# MemoryChip.net
KiCad netlist of a schematic drawn in Altium Designer
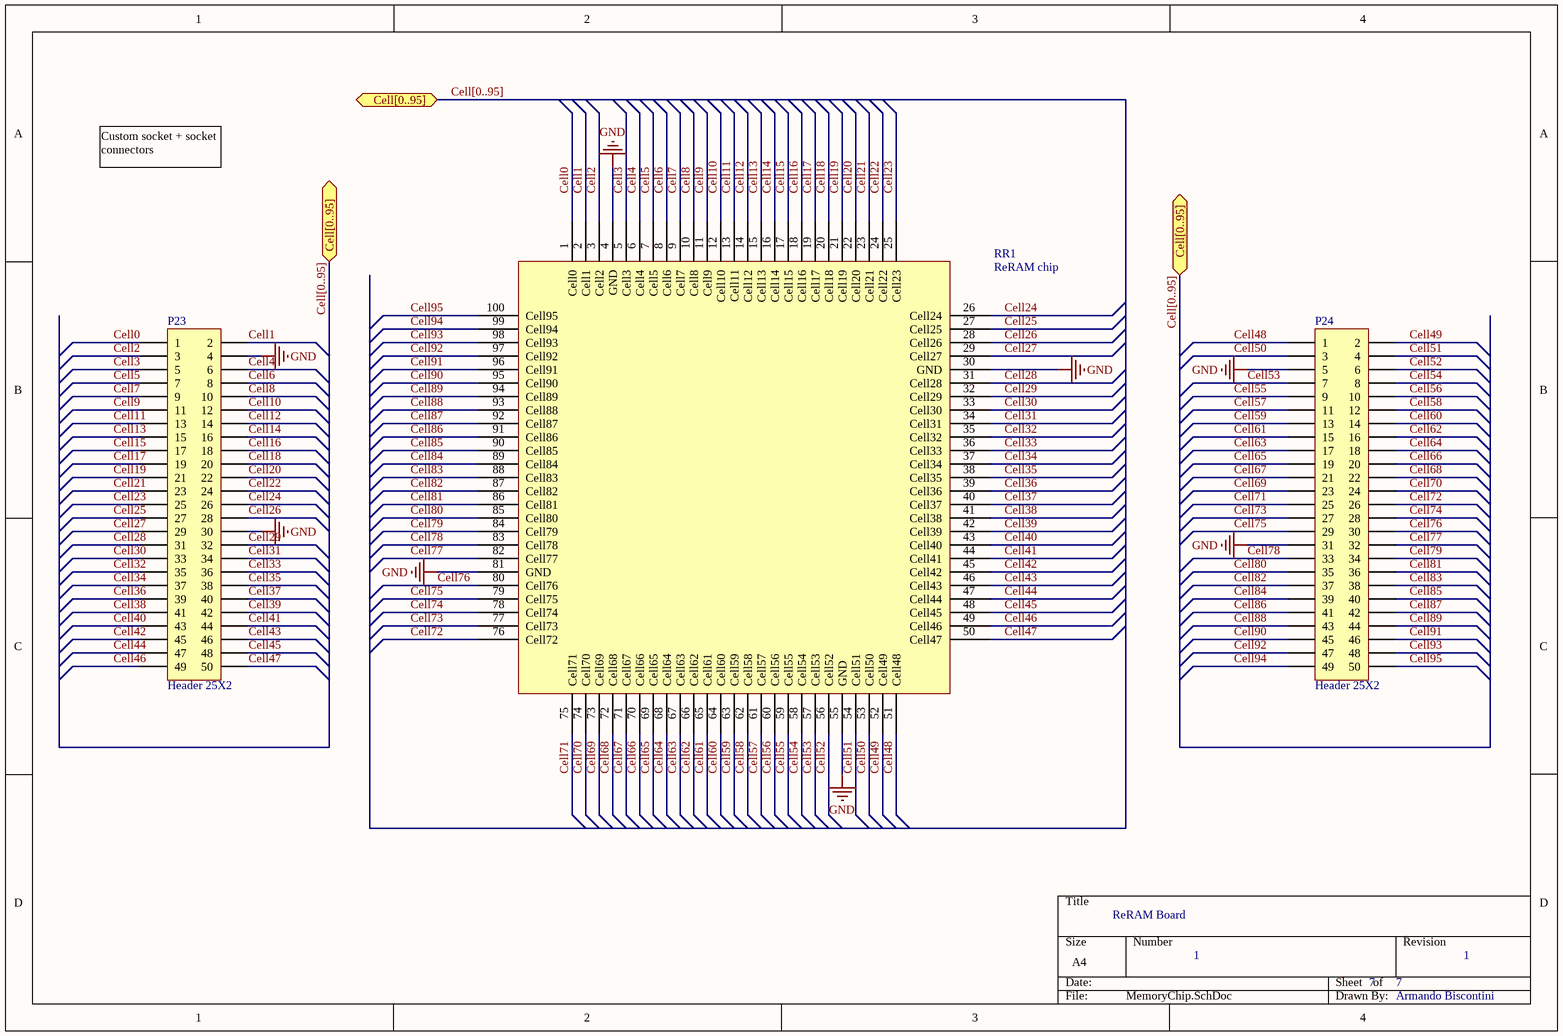
[diagram p0: MemoryChip.SchDoc]

(export (version "E")
  (design (tool "Eeschema 10.0.6"))
  (components
    (comp (ref "P23")
      (value "Header 25X2")
      (footprint "HDR2X25")
      (description "Header, 25-Pin, Dual row")
      (fields (field (name "PUBLISHER") "Altium Limited"))
      (libsource (lib "Miscellaneous Connectors") (part "Header 25X2"))
    )
    (comp (ref "P24")
      (value "Header 25X2")
      (footprint "HDR2X25")
      (description "Header, 25-Pin, Dual row")
      (fields (field (name "PUBLISHER") "Altium Limited"))
      (libsource (lib "Miscellaneous Connectors") (part "Header 25X2"))
    )
    (comp (ref "RR1")
      (value "ReRAM chip")
      (footprint "LSI-PLLGA100")
      (description "ReRAM chip on LSI-PLLGA100 custom socket")
      (libsource (lib "ReRAM_Board_library") (part "ReRAM_LSI-PLLGA100"))
    )
  )
  (nets
    (net (code "1") (name "/Cell0") (class "Default")
      (node (ref "P23") (pin "1") (pinfunction "1_1") (pintype "passive"))
      (node (ref "RR1") (pin "1") (pinfunction "Cell0_1") (pintype "passive"))
    )
    (net (code "2") (name "/Cell1") (class "Default")
      (node (ref "P23") (pin "2") (pinfunction "2_2") (pintype "passive"))
      (node (ref "RR1") (pin "2") (pinfunction "Cell1_2") (pintype "passive"))
    )
    (net (code "3") (name "/Cell2") (class "Default")
      (node (ref "P23") (pin "3") (pinfunction "3_3") (pintype "passive"))
      (node (ref "RR1") (pin "3") (pinfunction "Cell2_3") (pintype "passive"))
    )
    (net (code "4") (name "/Cell3") (class "Default")
      (node (ref "P23") (pin "5") (pinfunction "5_5") (pintype "passive"))
      (node (ref "RR1") (pin "5") (pinfunction "Cell3_5") (pintype "passive"))
    )
    (net (code "5") (name "/Cell4") (class "Default")
      (node (ref "P23") (pin "6") (pinfunction "6_6") (pintype "passive"))
      (node (ref "RR1") (pin "6") (pinfunction "Cell4_6") (pintype "passive"))
    )
    (net (code "6") (name "/Cell5") (class "Default")
      (node (ref "P23") (pin "7") (pinfunction "7_7") (pintype "passive"))
      (node (ref "RR1") (pin "7") (pinfunction "Cell5_7") (pintype "passive"))
    )
    (net (code "7") (name "/Cell6") (class "Default")
      (node (ref "P23") (pin "8") (pinfunction "8_8") (pintype "passive"))
      (node (ref "RR1") (pin "8") (pinfunction "Cell6_8") (pintype "passive"))
    )
    (net (code "8") (name "/Cell7") (class "Default")
      (node (ref "P23") (pin "9") (pinfunction "9_9") (pintype "passive"))
      (node (ref "RR1") (pin "9") (pinfunction "Cell7_9") (pintype "passive"))
    )
    (net (code "9") (name "/Cell8") (class "Default")
      (node (ref "P23") (pin "10") (pinfunction "10_10") (pintype "passive"))
      (node (ref "RR1") (pin "10") (pinfunction "Cell8_10") (pintype "passive"))
    )
    (net (code "10") (name "/Cell9") (class "Default")
      (node (ref "P23") (pin "11") (pinfunction "11_11") (pintype "passive"))
      (node (ref "RR1") (pin "11") (pinfunction "Cell9_11") (pintype "passive"))
    )
    (net (code "11") (name "/Cell10") (class "Default")
      (node (ref "P23") (pin "12") (pinfunction "12_12") (pintype "passive"))
      (node (ref "RR1") (pin "12") (pinfunction "Cell10_12") (pintype "passive"))
    )
    (net (code "12") (name "/Cell11") (class "Default")
      (node (ref "P23") (pin "13") (pinfunction "13_13") (pintype "passive"))
      (node (ref "RR1") (pin "13") (pinfunction "Cell11_13") (pintype "passive"))
    )
    (net (code "13") (name "/Cell12") (class "Default")
      (node (ref "P23") (pin "14") (pinfunction "14_14") (pintype "passive"))
      (node (ref "RR1") (pin "14") (pinfunction "Cell12_14") (pintype "passive"))
    )
    (net (code "14") (name "/Cell13") (class "Default")
      (node (ref "P23") (pin "15") (pinfunction "15_15") (pintype "passive"))
      (node (ref "RR1") (pin "15") (pinfunction "Cell13_15") (pintype "passive"))
    )
    (net (code "15") (name "/Cell14") (class "Default")
      (node (ref "P23") (pin "16") (pinfunction "16_16") (pintype "passive"))
      (node (ref "RR1") (pin "16") (pinfunction "Cell14_16") (pintype "passive"))
    )
    (net (code "16") (name "/Cell15") (class "Default")
      (node (ref "P23") (pin "17") (pinfunction "17_17") (pintype "passive"))
      (node (ref "RR1") (pin "17") (pinfunction "Cell15_17") (pintype "passive"))
    )
    (net (code "17") (name "/Cell16") (class "Default")
      (node (ref "P23") (pin "18") (pinfunction "18_18") (pintype "passive"))
      (node (ref "RR1") (pin "18") (pinfunction "Cell16_18") (pintype "passive"))
    )
    (net (code "18") (name "/Cell17") (class "Default")
      (node (ref "P23") (pin "19") (pinfunction "19_19") (pintype "passive"))
      (node (ref "RR1") (pin "19") (pinfunction "Cell17_19") (pintype "passive"))
    )
    (net (code "19") (name "/Cell18") (class "Default")
      (node (ref "P23") (pin "20") (pinfunction "20_20") (pintype "passive"))
      (node (ref "RR1") (pin "20") (pinfunction "Cell18_20") (pintype "passive"))
    )
    (net (code "20") (name "/Cell19") (class "Default")
      (node (ref "P23") (pin "21") (pinfunction "21_21") (pintype "passive"))
      (node (ref "RR1") (pin "21") (pinfunction "Cell19_21") (pintype "passive"))
    )
    (net (code "21") (name "/Cell20") (class "Default")
      (node (ref "P23") (pin "22") (pinfunction "22_22") (pintype "passive"))
      (node (ref "RR1") (pin "22") (pinfunction "Cell20_22") (pintype "passive"))
    )
    (net (code "22") (name "/Cell21") (class "Default")
      (node (ref "P23") (pin "23") (pinfunction "23_23") (pintype "passive"))
      (node (ref "RR1") (pin "23") (pinfunction "Cell21_23") (pintype "passive"))
    )
    (net (code "23") (name "/Cell22") (class "Default")
      (node (ref "P23") (pin "24") (pinfunction "24_24") (pintype "passive"))
      (node (ref "RR1") (pin "24") (pinfunction "Cell22_24") (pintype "passive"))
    )
    (net (code "24") (name "/Cell23") (class "Default")
      (node (ref "P23") (pin "25") (pinfunction "25_25") (pintype "passive"))
      (node (ref "RR1") (pin "25") (pinfunction "Cell23_25") (pintype "passive"))
    )
    (net (code "25") (name "/Cell24") (class "Default")
      (node (ref "P23") (pin "26") (pinfunction "26_26") (pintype "passive"))
      (node (ref "RR1") (pin "26") (pinfunction "Cell24_26") (pintype "passive"))
    )
    (net (code "26") (name "/Cell25") (class "Default")
      (node (ref "P23") (pin "27") (pinfunction "27_27") (pintype "passive"))
      (node (ref "RR1") (pin "27") (pinfunction "Cell25_27") (pintype "passive"))
    )
    (net (code "27") (name "/Cell26") (class "Default")
      (node (ref "P23") (pin "28") (pinfunction "28_28") (pintype "passive"))
      (node (ref "RR1") (pin "28") (pinfunction "Cell26_28") (pintype "passive"))
    )
    (net (code "28") (name "/Cell27") (class "Default")
      (node (ref "P23") (pin "29") (pinfunction "29_29") (pintype "passive"))
      (node (ref "RR1") (pin "29") (pinfunction "Cell27_29") (pintype "passive"))
    )
    (net (code "29") (name "/Cell28") (class "Default")
      (node (ref "P23") (pin "31") (pinfunction "31_31") (pintype "passive"))
      (node (ref "RR1") (pin "31") (pinfunction "Cell28_31") (pintype "passive"))
    )
    (net (code "30") (name "/Cell29") (class "Default")
      (node (ref "P23") (pin "32") (pinfunction "32_32") (pintype "passive"))
      (node (ref "RR1") (pin "32") (pinfunction "Cell29_32") (pintype "passive"))
    )
    (net (code "31") (name "/Cell30") (class "Default")
      (node (ref "P23") (pin "33") (pinfunction "33_33") (pintype "passive"))
      (node (ref "RR1") (pin "33") (pinfunction "Cell30_33") (pintype "passive"))
    )
    (net (code "32") (name "/Cell31") (class "Default")
      (node (ref "P23") (pin "34") (pinfunction "34_34") (pintype "passive"))
      (node (ref "RR1") (pin "34") (pinfunction "Cell31_34") (pintype "passive"))
    )
    (net (code "33") (name "/Cell32") (class "Default")
      (node (ref "P23") (pin "35") (pinfunction "35_35") (pintype "passive"))
      (node (ref "RR1") (pin "35") (pinfunction "Cell32_35") (pintype "passive"))
    )
    (net (code "34") (name "/Cell33") (class "Default")
      (node (ref "P23") (pin "36") (pinfunction "36_36") (pintype "passive"))
      (node (ref "RR1") (pin "36") (pinfunction "Cell33_36") (pintype "passive"))
    )
    (net (code "35") (name "/Cell34") (class "Default")
      (node (ref "P23") (pin "37") (pinfunction "37_37") (pintype "passive"))
      (node (ref "RR1") (pin "37") (pinfunction "Cell34_37") (pintype "passive"))
    )
    (net (code "36") (name "/Cell35") (class "Default")
      (node (ref "P23") (pin "38") (pinfunction "38_38") (pintype "passive"))
      (node (ref "RR1") (pin "38") (pinfunction "Cell35_38") (pintype "passive"))
    )
    (net (code "37") (name "/Cell36") (class "Default")
      (node (ref "P23") (pin "39") (pinfunction "39_39") (pintype "passive"))
      (node (ref "RR1") (pin "39") (pinfunction "Cell36_39") (pintype "passive"))
    )
    (net (code "38") (name "/Cell37") (class "Default")
      (node (ref "P23") (pin "40") (pinfunction "40_40") (pintype "passive"))
      (node (ref "RR1") (pin "40") (pinfunction "Cell37_40") (pintype "passive"))
    )
    (net (code "39") (name "/Cell38") (class "Default")
      (node (ref "P23") (pin "41") (pinfunction "41_41") (pintype "passive"))
      (node (ref "RR1") (pin "41") (pinfunction "Cell38_41") (pintype "passive"))
    )
    (net (code "40") (name "/Cell39") (class "Default")
      (node (ref "P23") (pin "42") (pinfunction "42_42") (pintype "passive"))
      (node (ref "RR1") (pin "42") (pinfunction "Cell39_42") (pintype "passive"))
    )
    (net (code "41") (name "/Cell40") (class "Default")
      (node (ref "P23") (pin "43") (pinfunction "43_43") (pintype "passive"))
      (node (ref "RR1") (pin "43") (pinfunction "Cell40_43") (pintype "passive"))
    )
    (net (code "42") (name "/Cell41") (class "Default")
      (node (ref "P23") (pin "44") (pinfunction "44_44") (pintype "passive"))
      (node (ref "RR1") (pin "44") (pinfunction "Cell41_44") (pintype "passive"))
    )
    (net (code "43") (name "/Cell42") (class "Default")
      (node (ref "P23") (pin "45") (pinfunction "45_45") (pintype "passive"))
      (node (ref "RR1") (pin "45") (pinfunction "Cell42_45") (pintype "passive"))
    )
    (net (code "44") (name "/Cell43") (class "Default")
      (node (ref "P23") (pin "46") (pinfunction "46_46") (pintype "passive"))
      (node (ref "RR1") (pin "46") (pinfunction "Cell43_46") (pintype "passive"))
    )
    (net (code "45") (name "/Cell44") (class "Default")
      (node (ref "P23") (pin "47") (pinfunction "47_47") (pintype "passive"))
      (node (ref "RR1") (pin "47") (pinfunction "Cell44_47") (pintype "passive"))
    )
    (net (code "46") (name "/Cell45") (class "Default")
      (node (ref "P23") (pin "48") (pinfunction "48_48") (pintype "passive"))
      (node (ref "RR1") (pin "48") (pinfunction "Cell45_48") (pintype "passive"))
    )
    (net (code "47") (name "/Cell46") (class "Default")
      (node (ref "P23") (pin "49") (pinfunction "49_49") (pintype "passive"))
      (node (ref "RR1") (pin "49") (pinfunction "Cell46_49") (pintype "passive"))
    )
    (net (code "48") (name "/Cell47") (class "Default")
      (node (ref "P23") (pin "50") (pinfunction "50_50") (pintype "passive"))
      (node (ref "RR1") (pin "50") (pinfunction "Cell47_50") (pintype "passive"))
    )
    (net (code "49") (name "/Cell48") (class "Default")
      (node (ref "P24") (pin "1") (pinfunction "1_1") (pintype "passive"))
      (node (ref "RR1") (pin "51") (pinfunction "Cell48_51") (pintype "passive"))
    )
    (net (code "50") (name "/Cell49") (class "Default")
      (node (ref "P24") (pin "2") (pinfunction "2_2") (pintype "passive"))
      (node (ref "RR1") (pin "52") (pinfunction "Cell49_52") (pintype "passive"))
    )
    (net (code "51") (name "/Cell50") (class "Default")
      (node (ref "P24") (pin "3") (pinfunction "3_3") (pintype "passive"))
      (node (ref "RR1") (pin "53") (pinfunction "Cell50_53") (pintype "passive"))
    )
    (net (code "52") (name "/Cell51") (class "Default")
      (node (ref "P24") (pin "4") (pinfunction "4_4") (pintype "passive"))
      (node (ref "RR1") (pin "54") (pinfunction "Cell51_54") (pintype "passive"))
    )
    (net (code "53") (name "/Cell52") (class "Default")
      (node (ref "P24") (pin "6") (pinfunction "6_6") (pintype "passive"))
      (node (ref "RR1") (pin "56") (pinfunction "Cell52_56") (pintype "passive"))
    )
    (net (code "54") (name "/Cell53") (class "Default")
      (node (ref "P24") (pin "7") (pinfunction "7_7") (pintype "passive"))
      (node (ref "RR1") (pin "57") (pinfunction "Cell53_57") (pintype "passive"))
    )
    (net (code "55") (name "/Cell54") (class "Default")
      (node (ref "P24") (pin "8") (pinfunction "8_8") (pintype "passive"))
      (node (ref "RR1") (pin "58") (pinfunction "Cell54_58") (pintype "passive"))
    )
    (net (code "56") (name "/Cell55") (class "Default")
      (node (ref "P24") (pin "9") (pinfunction "9_9") (pintype "passive"))
      (node (ref "RR1") (pin "59") (pinfunction "Cell55_59") (pintype "passive"))
    )
    (net (code "57") (name "/Cell56") (class "Default")
      (node (ref "P24") (pin "10") (pinfunction "10_10") (pintype "passive"))
      (node (ref "RR1") (pin "60") (pinfunction "Cell56_60") (pintype "passive"))
    )
    (net (code "58") (name "/Cell57") (class "Default")
      (node (ref "P24") (pin "11") (pinfunction "11_11") (pintype "passive"))
      (node (ref "RR1") (pin "61") (pinfunction "Cell57_61") (pintype "passive"))
    )
    (net (code "59") (name "/Cell58") (class "Default")
      (node (ref "P24") (pin "12") (pinfunction "12_12") (pintype "passive"))
      (node (ref "RR1") (pin "62") (pinfunction "Cell58_62") (pintype "passive"))
    )
    (net (code "60") (name "/Cell59") (class "Default")
      (node (ref "P24") (pin "13") (pinfunction "13_13") (pintype "passive"))
      (node (ref "RR1") (pin "63") (pinfunction "Cell59_63") (pintype "passive"))
    )
    (net (code "61") (name "/Cell60") (class "Default")
      (node (ref "P24") (pin "14") (pinfunction "14_14") (pintype "passive"))
      (node (ref "RR1") (pin "64") (pinfunction "Cell60_64") (pintype "passive"))
    )
    (net (code "62") (name "/Cell61") (class "Default")
      (node (ref "P24") (pin "15") (pinfunction "15_15") (pintype "passive"))
      (node (ref "RR1") (pin "65") (pinfunction "Cell61_65") (pintype "passive"))
    )
    (net (code "63") (name "/Cell62") (class "Default")
      (node (ref "P24") (pin "16") (pinfunction "16_16") (pintype "passive"))
      (node (ref "RR1") (pin "66") (pinfunction "Cell62_66") (pintype "passive"))
    )
    (net (code "64") (name "/Cell63") (class "Default")
      (node (ref "P24") (pin "17") (pinfunction "17_17") (pintype "passive"))
      (node (ref "RR1") (pin "67") (pinfunction "Cell63_67") (pintype "passive"))
    )
    (net (code "65") (name "/Cell64") (class "Default")
      (node (ref "P24") (pin "18") (pinfunction "18_18") (pintype "passive"))
      (node (ref "RR1") (pin "68") (pinfunction "Cell64_68") (pintype "passive"))
    )
    (net (code "66") (name "/Cell65") (class "Default")
      (node (ref "P24") (pin "19") (pinfunction "19_19") (pintype "passive"))
      (node (ref "RR1") (pin "69") (pinfunction "Cell65_69") (pintype "passive"))
    )
    (net (code "67") (name "/Cell66") (class "Default")
      (node (ref "P24") (pin "20") (pinfunction "20_20") (pintype "passive"))
      (node (ref "RR1") (pin "70") (pinfunction "Cell66_70") (pintype "passive"))
    )
    (net (code "68") (name "/Cell67") (class "Default")
      (node (ref "P24") (pin "21") (pinfunction "21_21") (pintype "passive"))
      (node (ref "RR1") (pin "71") (pinfunction "Cell67_71") (pintype "passive"))
    )
    (net (code "69") (name "/Cell68") (class "Default")
      (node (ref "P24") (pin "22") (pinfunction "22_22") (pintype "passive"))
      (node (ref "RR1") (pin "72") (pinfunction "Cell68_72") (pintype "passive"))
    )
    (net (code "70") (name "/Cell69") (class "Default")
      (node (ref "P24") (pin "23") (pinfunction "23_23") (pintype "passive"))
      (node (ref "RR1") (pin "73") (pinfunction "Cell69_73") (pintype "passive"))
    )
    (net (code "71") (name "/Cell70") (class "Default")
      (node (ref "P24") (pin "24") (pinfunction "24_24") (pintype "passive"))
      (node (ref "RR1") (pin "74") (pinfunction "Cell70_74") (pintype "passive"))
    )
    (net (code "72") (name "/Cell71") (class "Default")
      (node (ref "P24") (pin "25") (pinfunction "25_25") (pintype "passive"))
      (node (ref "RR1") (pin "75") (pinfunction "Cell71_75") (pintype "passive"))
    )
    (net (code "73") (name "/Cell72") (class "Default")
      (node (ref "P24") (pin "26") (pinfunction "26_26") (pintype "passive"))
      (node (ref "RR1") (pin "76") (pinfunction "Cell72_76") (pintype "passive"))
    )
    (net (code "74") (name "/Cell73") (class "Default")
      (node (ref "P24") (pin "27") (pinfunction "27_27") (pintype "passive"))
      (node (ref "RR1") (pin "77") (pinfunction "Cell73_77") (pintype "passive"))
    )
    (net (code "75") (name "/Cell74") (class "Default")
      (node (ref "P24") (pin "28") (pinfunction "28_28") (pintype "passive"))
      (node (ref "RR1") (pin "78") (pinfunction "Cell74_78") (pintype "passive"))
    )
    (net (code "76") (name "/Cell75") (class "Default")
      (node (ref "P24") (pin "29") (pinfunction "29_29") (pintype "passive"))
      (node (ref "RR1") (pin "79") (pinfunction "Cell75_79") (pintype "passive"))
    )
    (net (code "77") (name "/Cell76") (class "Default")
      (node (ref "P24") (pin "30") (pinfunction "30_30") (pintype "passive"))
      (node (ref "RR1") (pin "80") (pinfunction "Cell76_80") (pintype "passive"))
    )
    (net (code "78") (name "/Cell77") (class "Default")
      (node (ref "P24") (pin "32") (pinfunction "32_32") (pintype "passive"))
      (node (ref "RR1") (pin "82") (pinfunction "Cell77_82") (pintype "passive"))
    )
    (net (code "79") (name "/Cell78") (class "Default")
      (node (ref "P24") (pin "33") (pinfunction "33_33") (pintype "passive"))
      (node (ref "RR1") (pin "83") (pinfunction "Cell78_83") (pintype "passive"))
    )
    (net (code "80") (name "/Cell79") (class "Default")
      (node (ref "P24") (pin "34") (pinfunction "34_34") (pintype "passive"))
      (node (ref "RR1") (pin "84") (pinfunction "Cell79_84") (pintype "passive"))
    )
    (net (code "81") (name "/Cell80") (class "Default")
      (node (ref "P24") (pin "35") (pinfunction "35_35") (pintype "passive"))
      (node (ref "RR1") (pin "85") (pinfunction "Cell80_85") (pintype "passive"))
    )
    (net (code "82") (name "/Cell81") (class "Default")
      (node (ref "P24") (pin "36") (pinfunction "36_36") (pintype "passive"))
      (node (ref "RR1") (pin "86") (pinfunction "Cell81_86") (pintype "passive"))
    )
    (net (code "83") (name "/Cell82") (class "Default")
      (node (ref "P24") (pin "37") (pinfunction "37_37") (pintype "passive"))
      (node (ref "RR1") (pin "87") (pinfunction "Cell82_87") (pintype "passive"))
    )
    (net (code "84") (name "/Cell83") (class "Default")
      (node (ref "P24") (pin "38") (pinfunction "38_38") (pintype "passive"))
      (node (ref "RR1") (pin "88") (pinfunction "Cell83_88") (pintype "passive"))
    )
    (net (code "85") (name "/Cell84") (class "Default")
      (node (ref "P24") (pin "39") (pinfunction "39_39") (pintype "passive"))
      (node (ref "RR1") (pin "89") (pinfunction "Cell84_89") (pintype "passive"))
    )
    (net (code "86") (name "/Cell85") (class "Default")
      (node (ref "P24") (pin "40") (pinfunction "40_40") (pintype "passive"))
      (node (ref "RR1") (pin "90") (pinfunction "Cell85_90") (pintype "passive"))
    )
    (net (code "87") (name "/Cell86") (class "Default")
      (node (ref "P24") (pin "41") (pinfunction "41_41") (pintype "passive"))
      (node (ref "RR1") (pin "91") (pinfunction "Cell86_91") (pintype "passive"))
    )
    (net (code "88") (name "/Cell87") (class "Default")
      (node (ref "P24") (pin "42") (pinfunction "42_42") (pintype "passive"))
      (node (ref "RR1") (pin "92") (pinfunction "Cell87_92") (pintype "passive"))
    )
    (net (code "89") (name "/Cell88") (class "Default")
      (node (ref "P24") (pin "43") (pinfunction "43_43") (pintype "passive"))
      (node (ref "RR1") (pin "93") (pinfunction "Cell88_93") (pintype "passive"))
    )
    (net (code "90") (name "/Cell89") (class "Default")
      (node (ref "P24") (pin "44") (pinfunction "44_44") (pintype "passive"))
      (node (ref "RR1") (pin "94") (pinfunction "Cell89_94") (pintype "passive"))
    )
    (net (code "91") (name "/Cell90") (class "Default")
      (node (ref "P24") (pin "45") (pinfunction "45_45") (pintype "passive"))
      (node (ref "RR1") (pin "95") (pinfunction "Cell90_95") (pintype "passive"))
    )
    (net (code "92") (name "/Cell91") (class "Default")
      (node (ref "P24") (pin "46") (pinfunction "46_46") (pintype "passive"))
      (node (ref "RR1") (pin "96") (pinfunction "Cell91_96") (pintype "passive"))
    )
    (net (code "93") (name "/Cell92") (class "Default")
      (node (ref "P24") (pin "47") (pinfunction "47_47") (pintype "passive"))
      (node (ref "RR1") (pin "97") (pinfunction "Cell92_97") (pintype "passive"))
    )
    (net (code "94") (name "/Cell93") (class "Default")
      (node (ref "P24") (pin "48") (pinfunction "48_48") (pintype "passive"))
      (node (ref "RR1") (pin "98") (pinfunction "Cell93_98") (pintype "passive"))
    )
    (net (code "95") (name "/Cell94") (class "Default")
      (node (ref "P24") (pin "49") (pinfunction "49_49") (pintype "passive"))
      (node (ref "RR1") (pin "99") (pinfunction "Cell94_99") (pintype "passive"))
    )
    (net (code "96") (name "/Cell95") (class "Default")
      (node (ref "P24") (pin "50") (pinfunction "50_50") (pintype "passive"))
      (node (ref "RR1") (pin "100") (pinfunction "Cell95_100") (pintype "passive"))
    )
    (net (code "98") (name "GND") (class "Default")
      (node (ref "P23") (pin "30") (pinfunction "30_30") (pintype "passive"))
      (node (ref "P23") (pin "4") (pinfunction "4_4") (pintype "passive"))
      (node (ref "P24") (pin "31") (pinfunction "31_31") (pintype "passive"))
      (node (ref "P24") (pin "5") (pinfunction "5_5") (pintype "passive"))
      (node (ref "RR1") (pin "30") (pinfunction "GND_30") (pintype "passive"))
      (node (ref "RR1") (pin "4") (pinfunction "GND_4") (pintype "passive"))
      (node (ref "RR1") (pin "55") (pinfunction "GND_55") (pintype "passive"))
      (node (ref "RR1") (pin "81") (pinfunction "GND_81") (pintype "passive"))
    )
  )
)
